# EEZ_PSU_post-regulator_r4B45.net
KiCad netlist of a schematic drawn in EAGLE
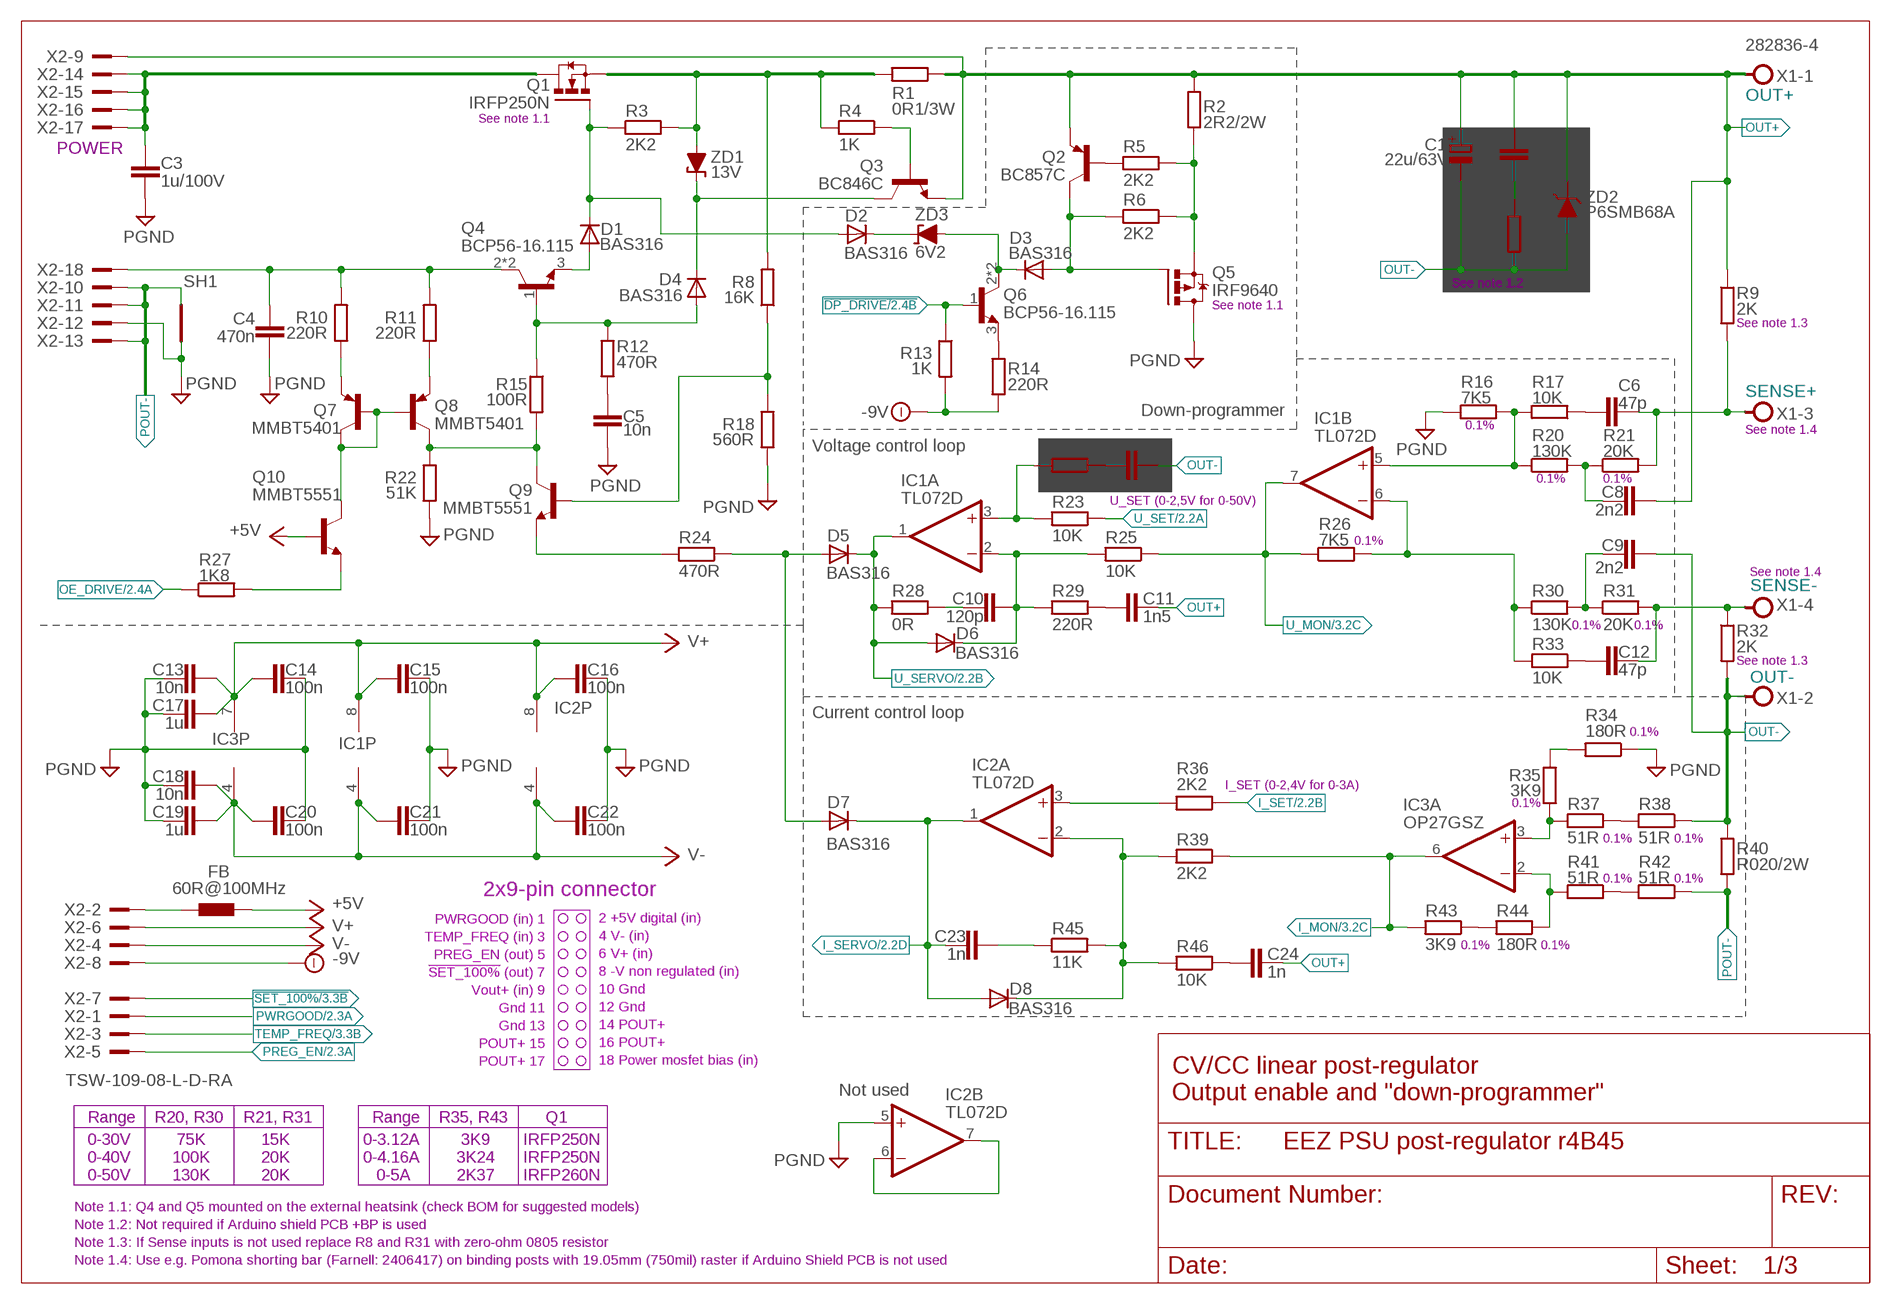
[diagram p0: schematic, sheet 1]
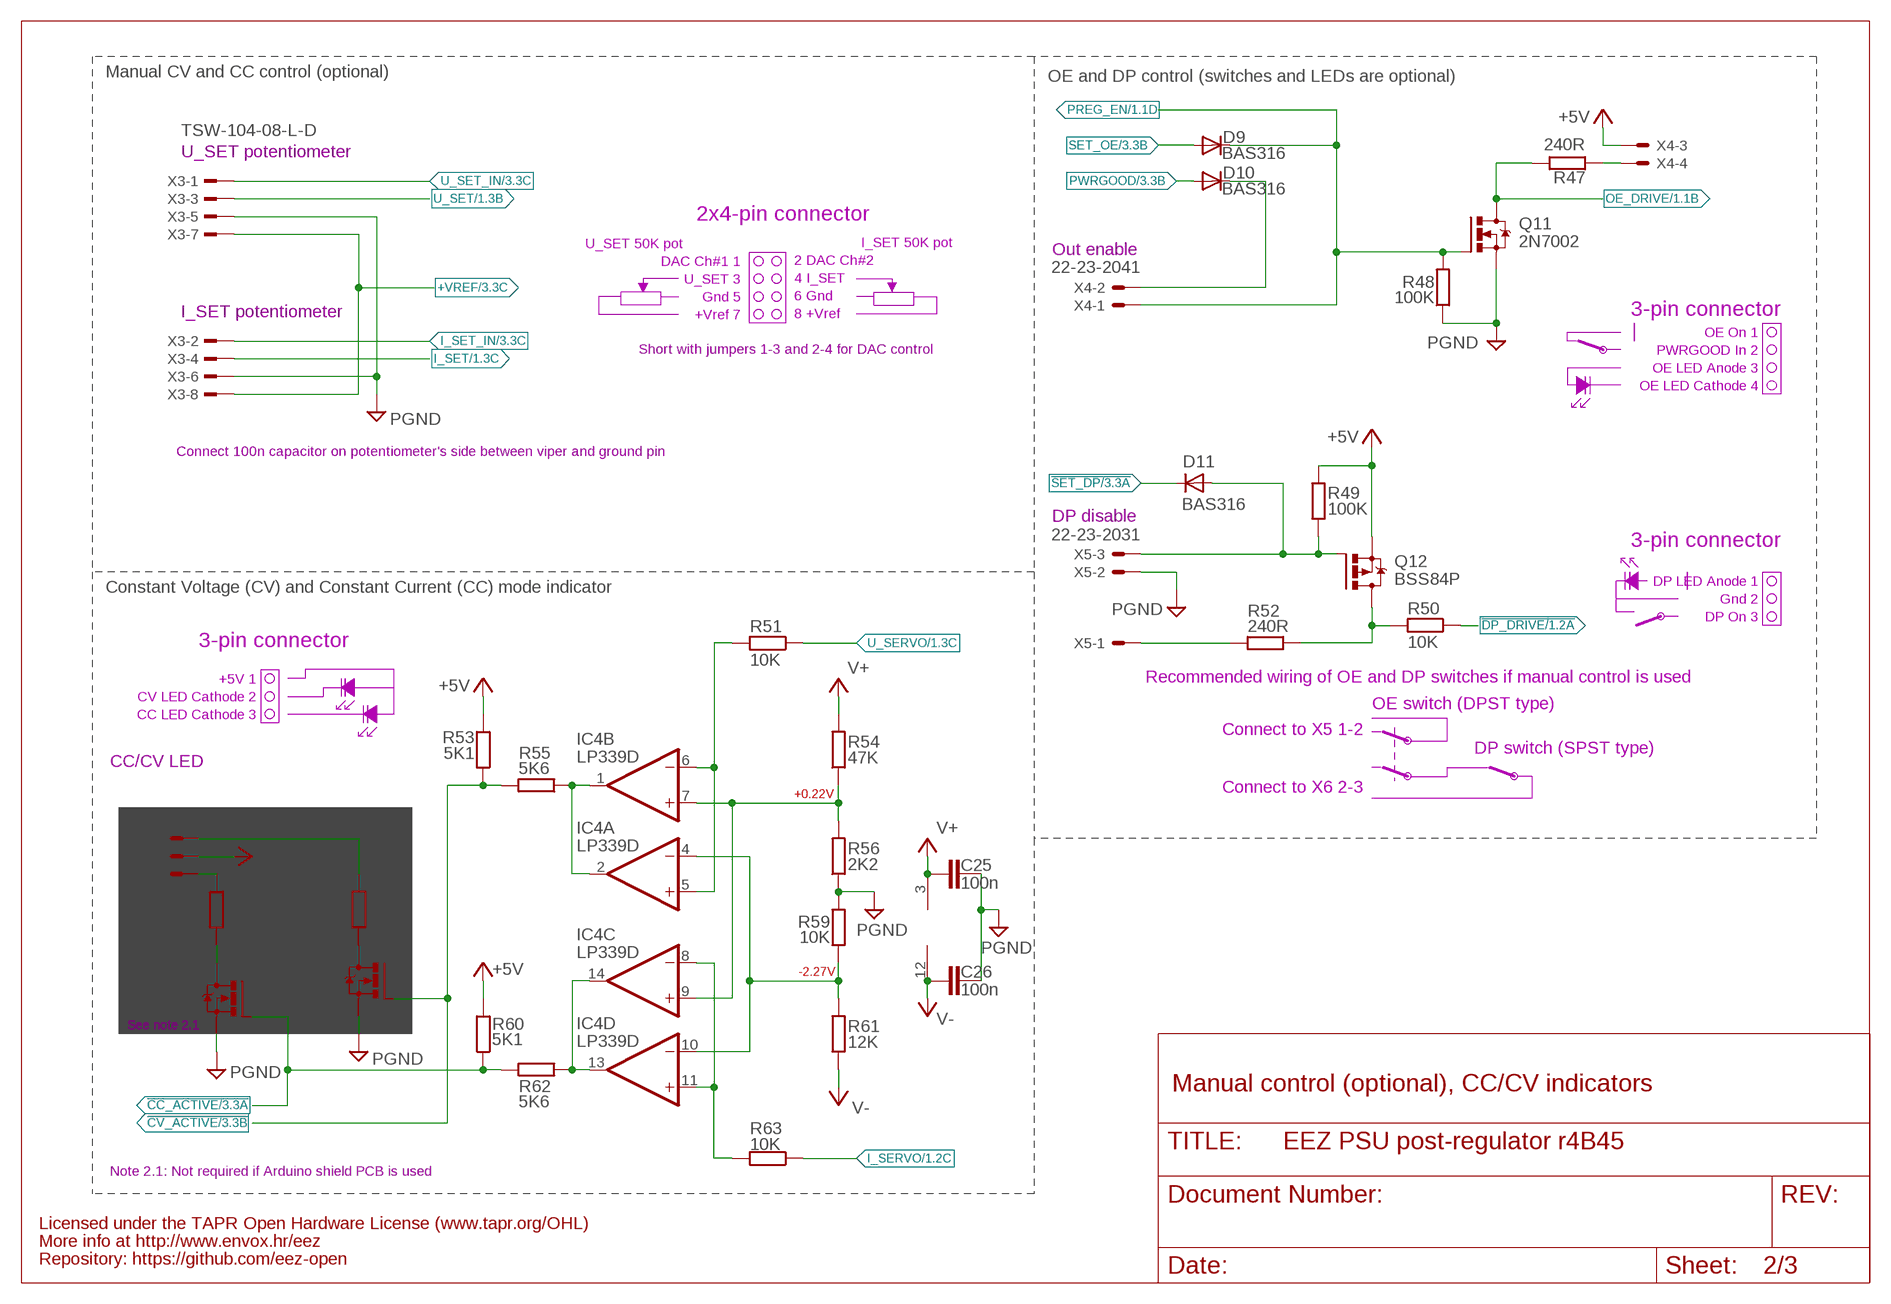
[diagram p1: schematic, sheet 2]
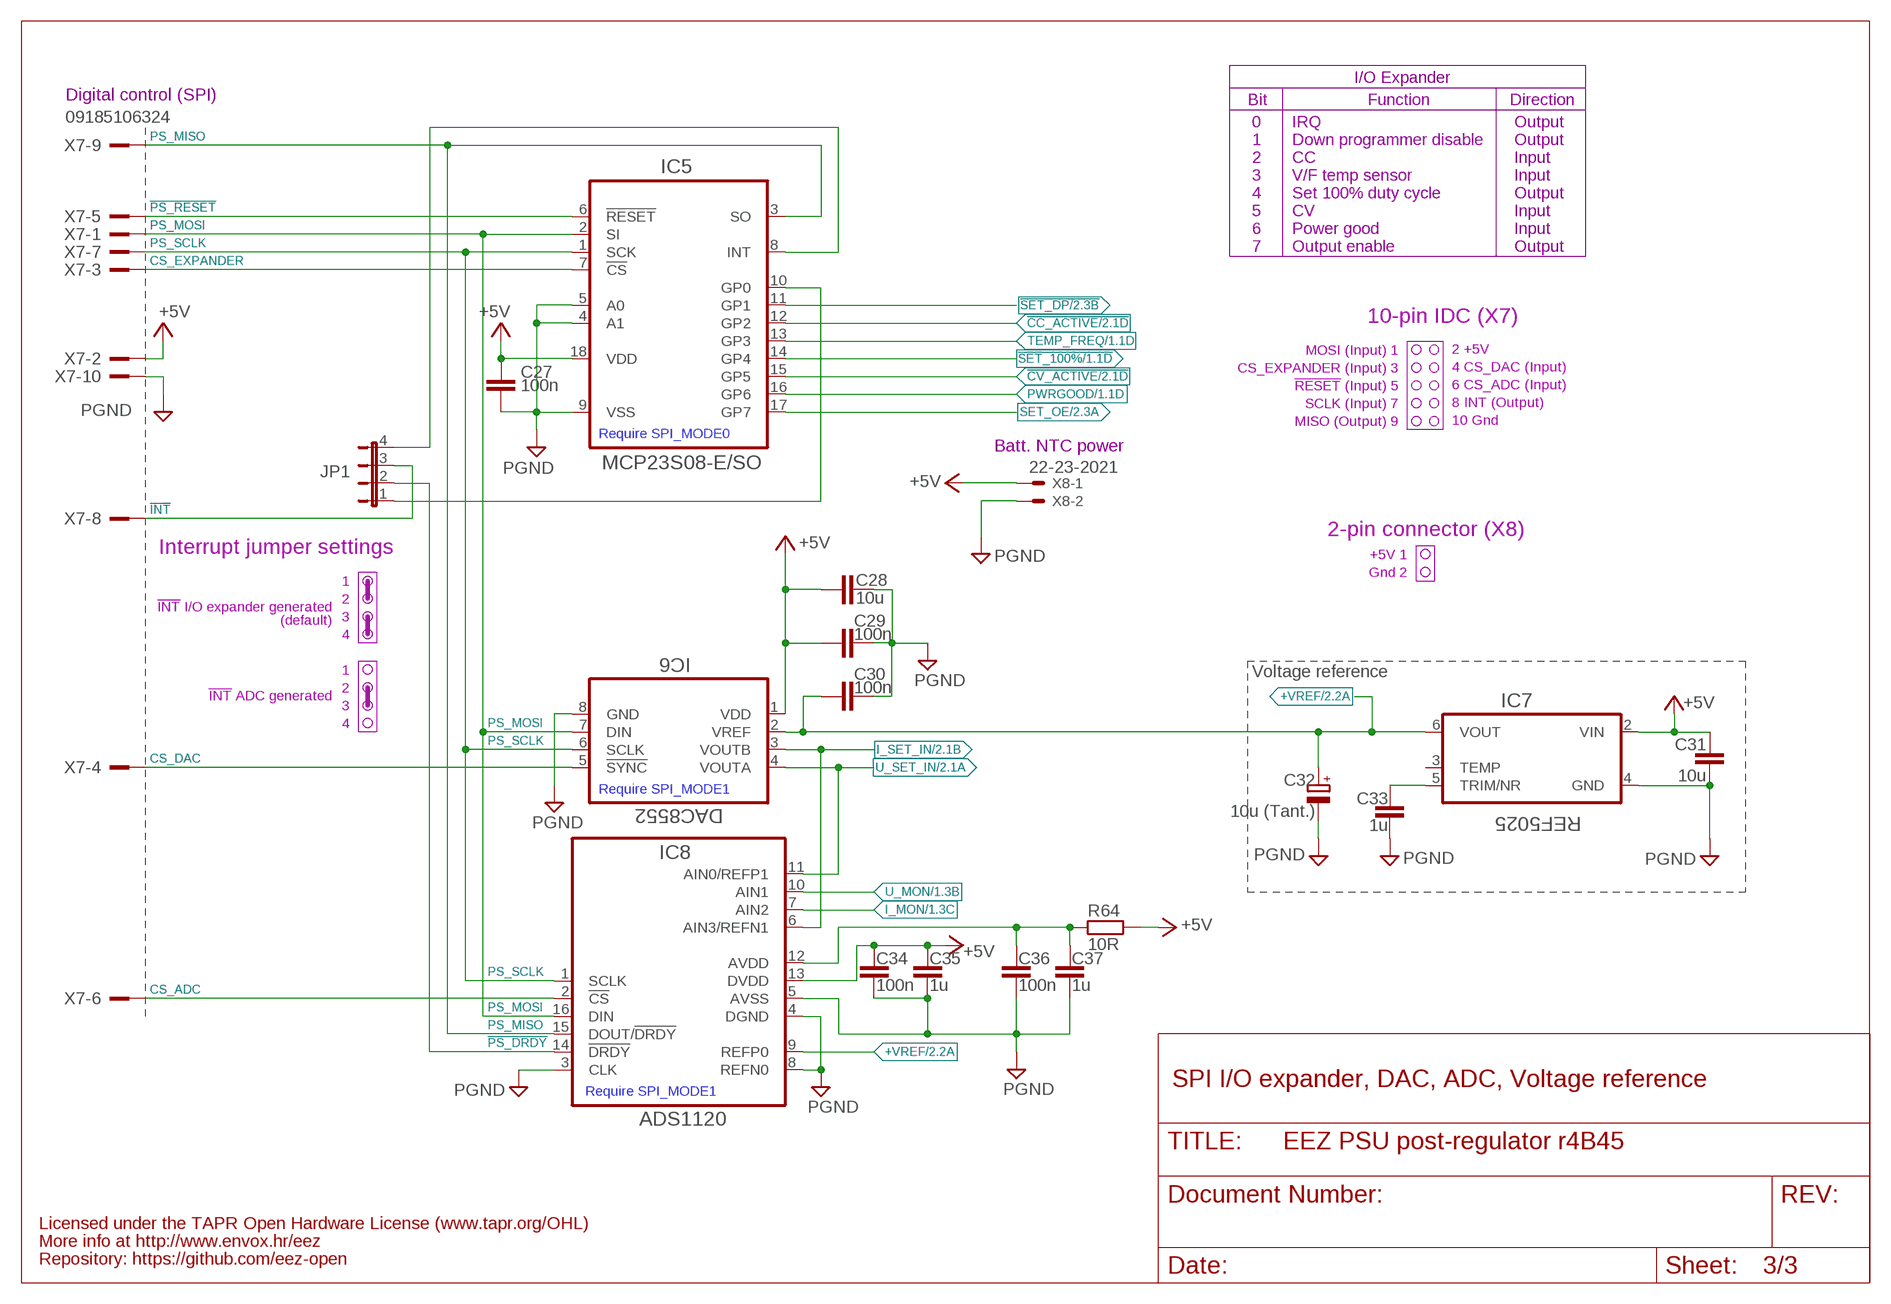
[diagram p2: schematic, sheet 3]

(export (version "E")
  (design (tool "Eeschema 10.0.6"))
  (components
    (comp (ref "C1")
      (value "22u/63V")
      (footprint "eagle-import:CAPAE660X610N_COMBO2")
      (libsource (lib "eagle-import") (part "ECAPEEEFK+2.5MM"))
    )
    (comp (ref "C2")
      (value "470n")
      (footprint "eagle-import:C1812")
      (libsource (lib "eagle-import") (part "C-EUC1812"))
    )
    (comp (ref "C3")
      (value "1u/100V")
      (footprint "eagle-import:C1206")
      (libsource (lib "eagle-import") (part "C-EUC1206"))
    )
    (comp (ref "C4")
      (value "470n")
      (footprint "eagle-import:C1812")
      (libsource (lib "eagle-import") (part "C-EUC1812"))
    )
    (comp (ref "C5")
      (value "10n")
      (footprint "eagle-import:C0805")
      (libsource (lib "eagle-import") (part "C-EUC0805"))
    )
    (comp (ref "C6")
      (value "47p")
      (footprint "eagle-import:C0805")
      (libsource (lib "eagle-import") (part "C-EUC0805"))
    )
    (comp (ref "C7")
      (value "1n5")
      (footprint "eagle-import:C0805")
      (libsource (lib "eagle-import") (part "C-EUC0805"))
    )
    (comp (ref "C8")
      (value "2n2")
      (footprint "eagle-import:C0805")
      (libsource (lib "eagle-import") (part "C-EUC0805"))
    )
    (comp (ref "C9")
      (value "2n2")
      (footprint "eagle-import:C0805")
      (libsource (lib "eagle-import") (part "C-EUC0805"))
    )
    (comp (ref "C10")
      (value "120p")
      (footprint "eagle-import:C0805")
      (libsource (lib "eagle-import") (part "C-EUC0805"))
    )
    (comp (ref "C11")
      (value "1n5")
      (footprint "eagle-import:C0805")
      (libsource (lib "eagle-import") (part "C-EUC0805"))
    )
    (comp (ref "C12")
      (value "47p")
      (footprint "eagle-import:C0805")
      (libsource (lib "eagle-import") (part "C-EUC0805"))
    )
    (comp (ref "C13")
      (value "10n")
      (footprint "eagle-import:C0805")
      (libsource (lib "eagle-import") (part "C-EUC0805"))
    )
    (comp (ref "C14")
      (value "100n")
      (footprint "eagle-import:C0603")
      (libsource (lib "eagle-import") (part "C-EUC0603"))
    )
    (comp (ref "C15")
      (value "100n")
      (footprint "eagle-import:C0603")
      (libsource (lib "eagle-import") (part "C-EUC0603"))
    )
    (comp (ref "C16")
      (value "100n")
      (footprint "eagle-import:C0603")
      (libsource (lib "eagle-import") (part "C-EUC0603"))
    )
    (comp (ref "C17")
      (value "1u")
      (footprint "eagle-import:C0805")
      (libsource (lib "eagle-import") (part "C-EUC0805"))
    )
    (comp (ref "C18")
      (value "10n")
      (footprint "eagle-import:C0805")
      (libsource (lib "eagle-import") (part "C-EUC0805"))
    )
    (comp (ref "C19")
      (value "1u")
      (footprint "eagle-import:C0805")
      (libsource (lib "eagle-import") (part "C-EUC0805"))
    )
    (comp (ref "C20")
      (value "100n")
      (footprint "eagle-import:C0603")
      (libsource (lib "eagle-import") (part "C-EUC0603"))
    )
    (comp (ref "C21")
      (value "100n")
      (footprint "eagle-import:C0603")
      (libsource (lib "eagle-import") (part "C-EUC0603"))
    )
    (comp (ref "C22")
      (value "100n")
      (footprint "eagle-import:C0603")
      (libsource (lib "eagle-import") (part "C-EUC0603"))
    )
    (comp (ref "C23")
      (value "1n")
      (footprint "eagle-import:C0805")
      (libsource (lib "eagle-import") (part "C-EUC0805"))
    )
    (comp (ref "C24")
      (value "1n")
      (footprint "eagle-import:C0805")
      (libsource (lib "eagle-import") (part "C-EUC0805"))
    )
    (comp (ref "D1")
      (value "BAS316")
      (footprint "eagle-import:SOD323-W")
      (libsource (lib "eagle-import") (part "DIODE-SOD323-W"))
    )
    (comp (ref "D2")
      (value "BAS316")
      (footprint "eagle-import:SOD323-W")
      (libsource (lib "eagle-import") (part "DIODE-SOD323-W"))
    )
    (comp (ref "D3")
      (value "BAS316")
      (footprint "eagle-import:SOD323-W")
      (libsource (lib "eagle-import") (part "DIODE-SOD323-W"))
    )
    (comp (ref "D4")
      (value "BAS316")
      (footprint "eagle-import:SOD323-W")
      (libsource (lib "eagle-import") (part "DIODE-SOD323-W"))
    )
    (comp (ref "D5")
      (value "BAS316")
      (footprint "eagle-import:SOD323-W")
      (libsource (lib "eagle-import") (part "DIODE-SOD323-W"))
    )
    (comp (ref "D6")
      (value "BAS316")
      (footprint "eagle-import:SOD323-W")
      (libsource (lib "eagle-import") (part "DIODE-SOD323-W"))
    )
    (comp (ref "D7")
      (value "BAS316")
      (footprint "eagle-import:SOD323-W")
      (libsource (lib "eagle-import") (part "DIODE-SOD323-W"))
    )
    (comp (ref "D8")
      (value "BAS316")
      (footprint "eagle-import:SOD323-W")
      (libsource (lib "eagle-import") (part "DIODE-SOD323-W"))
    )
    (comp (ref "FB")
      (value "60R@100MHz")
      (footprint "eagle-import:BEAD0603")
      (libsource (lib "eagle-import") (part "FERRITE_BEAD0603"))
    )
    (comp (ref "IC1")
      (value "TL072D")
      (footprint "eagle-import:SOIC127P600X173-8N")
      (libsource (lib "eagle-import") (part "TL072SOIC8"))
    )
    (comp (ref "IC2")
      (value "TL072D")
      (footprint "eagle-import:SOIC127P600X173-8N")
      (libsource (lib "eagle-import") (part "TL072SOIC8"))
    )
    (comp (ref "IC3")
      (value "OP27GSZ")
      (footprint "eagle-import:SOIC127P600X173-8N")
      (libsource (lib "eagle-import") (part "OP27GSZSO8"))
    )
    (comp (ref "Q1")
      (value "IRFP250N")
      (footprint "eagle-import:TO247BV")
      (libsource (lib "eagle-import") (part "IRFP240"))
    )
    (comp (ref "Q2")
      (value "BC857C")
      (footprint "eagle-import:SOT23-BEC")
      (libsource (lib "eagle-import") (part "-PNP-SOT23-BECBC857C"))
    )
    (comp (ref "Q3")
      (value "BC846C")
      (footprint "eagle-import:SOT23-BEC")
      (libsource (lib "eagle-import") (part "-NPN-SOT23-BECBC846B"))
    )
    (comp (ref "Q4")
      (value "BCP56-16.115")
      (footprint "eagle-import:SOT230P700X180-4N")
      (libsource (lib "eagle-import") (part "BCP56"))
    )
    (comp (ref "Q5")
      (value "IRF9640")
      (footprint "eagle-import:TO220B-VMOS")
      (libsource (lib "eagle-import") (part "IRF9640"))
    )
    (comp (ref "Q6")
      (value "BCP56-16.115")
      (footprint "eagle-import:SOT230P700X180-4N")
      (libsource (lib "eagle-import") (part "BCP56"))
    )
    (comp (ref "Q7")
      (value "MMBT5401")
      (footprint "eagle-import:SOT23-BEC")
      (libsource (lib "eagle-import") (part "-PNP-SOT23-BECBC857B"))
    )
    (comp (ref "Q8")
      (value "MMBT5401")
      (footprint "eagle-import:SOT23-BEC")
      (libsource (lib "eagle-import") (part "-PNP-SOT23-BECBC857B"))
    )
    (comp (ref "Q9")
      (value "MMBT5551")
      (footprint "eagle-import:SOT23-BEC")
      (libsource (lib "eagle-import") (part "-NPN-SOT23-BECMMBT5551LT1"))
    )
    (comp (ref "Q10")
      (value "MMBT5551")
      (footprint "eagle-import:SOT23-BEC")
      (libsource (lib "eagle-import") (part "-NPN-SOT23-BECMMBT5551LT1"))
    )
    (comp (ref "R1")
      (value "0R1/3W")
      (footprint "eagle-import:0411V")
      (libsource (lib "eagle-import") (part "R-EU_0411/3V"))
    )
    (comp (ref "R2")
      (value "2R2/2W")
      (footprint "eagle-import:0411V")
      (libsource (lib "eagle-import") (part "R-EU_0411/3V"))
    )
    (comp (ref "R3")
      (value "2K2")
      (footprint "eagle-import:R0805")
      (libsource (lib "eagle-import") (part "R-EU_R0805"))
    )
    (comp (ref "R4")
      (value "1K")
      (footprint "eagle-import:R0805")
      (libsource (lib "eagle-import") (part "R-EU_R0805"))
    )
    (comp (ref "R5")
      (value "2K2")
      (footprint "eagle-import:R0805")
      (libsource (lib "eagle-import") (part "R-EU_R0805"))
    )
    (comp (ref "R6")
      (value "2K2")
      (footprint "eagle-import:R0805")
      (libsource (lib "eagle-import") (part "R-EU_R0805"))
    )
    (comp (ref "R7")
      (value "1R")
      (footprint "eagle-import:R0805")
      (libsource (lib "eagle-import") (part "R-EU_R0805"))
    )
    (comp (ref "R8")
      (value "16K")
      (footprint "eagle-import:R0805")
      (libsource (lib "eagle-import") (part "R-EU_R0805"))
    )
    (comp (ref "R9")
      (value "2K")
      (footprint "eagle-import:R0805")
      (libsource (lib "eagle-import") (part "R-EU_R0805"))
    )
    (comp (ref "R10")
      (value "220R")
      (footprint "eagle-import:R0805")
      (libsource (lib "eagle-import") (part "R-EU_R0805"))
    )
    (comp (ref "R11")
      (value "220R")
      (footprint "eagle-import:R0805")
      (libsource (lib "eagle-import") (part "R-EU_R0805"))
    )
    (comp (ref "R12")
      (value "470R")
      (footprint "eagle-import:R0805")
      (libsource (lib "eagle-import") (part "R-EU_R0805"))
    )
    (comp (ref "R13")
      (value "1K")
      (footprint "eagle-import:R0805")
      (libsource (lib "eagle-import") (part "R-EU_R0805"))
    )
    (comp (ref "R14")
      (value "220R")
      (footprint "eagle-import:R0805")
      (libsource (lib "eagle-import") (part "R-EU_R0805"))
    )
    (comp (ref "R15")
      (value "100R")
      (footprint "eagle-import:R0805")
      (libsource (lib "eagle-import") (part "R-EU_R0805"))
    )
    (comp (ref "R16")
      (value "7K5")
      (footprint "eagle-import:R0805")
      (libsource (lib "eagle-import") (part "R-EU_R0805"))
    )
    (comp (ref "R17")
      (value "10K")
      (footprint "eagle-import:R0805")
      (libsource (lib "eagle-import") (part "R-EU_R0805"))
    )
    (comp (ref "R18")
      (value "560R")
      (footprint "eagle-import:R0805")
      (libsource (lib "eagle-import") (part "R-EU_R0805"))
    )
    (comp (ref "R19")
      (value "220R")
      (footprint "eagle-import:R0805")
      (libsource (lib "eagle-import") (part "R-EU_R0805"))
    )
    (comp (ref "R20")
      (value "130K")
      (footprint "eagle-import:R0805")
      (libsource (lib "eagle-import") (part "R-EU_R0805"))
    )
    (comp (ref "R21")
      (value "20K")
      (footprint "eagle-import:R0805")
      (libsource (lib "eagle-import") (part "R-EU_R0805"))
    )
    (comp (ref "R22")
      (value "51K")
      (footprint "eagle-import:R0805")
      (libsource (lib "eagle-import") (part "R-EU_R0805"))
    )
    (comp (ref "R23")
      (value "10K")
      (footprint "eagle-import:R0805")
      (libsource (lib "eagle-import") (part "R-EU_R0805"))
    )
    (comp (ref "R24")
      (value "470R")
      (footprint "eagle-import:R0805")
      (libsource (lib "eagle-import") (part "R-EU_R0805"))
    )
    (comp (ref "R25")
      (value "10K")
      (footprint "eagle-import:R0805")
      (libsource (lib "eagle-import") (part "R-EU_R0805"))
    )
    (comp (ref "R26")
      (value "7K5")
      (footprint "eagle-import:R0805")
      (libsource (lib "eagle-import") (part "R-EU_R0805"))
    )
    (comp (ref "R27")
      (value "1K8")
      (footprint "eagle-import:R0805")
      (libsource (lib "eagle-import") (part "R-EU_R0805"))
    )
    (comp (ref "R28")
      (value "0R")
      (footprint "eagle-import:R0805")
      (libsource (lib "eagle-import") (part "R-EU_R0805"))
    )
    (comp (ref "R29")
      (value "220R")
      (footprint "eagle-import:R0805")
      (libsource (lib "eagle-import") (part "R-EU_R0805"))
    )
    (comp (ref "R30")
      (value "130K")
      (footprint "eagle-import:R0805")
      (libsource (lib "eagle-import") (part "R-EU_R0805"))
    )
    (comp (ref "R31")
      (value "20K")
      (footprint "eagle-import:R0805")
      (libsource (lib "eagle-import") (part "R-EU_R0805"))
    )
    (comp (ref "R32")
      (value "2K")
      (footprint "eagle-import:R0805")
      (libsource (lib "eagle-import") (part "R-EU_R0805"))
    )
    (comp (ref "R33")
      (value "10K")
      (footprint "eagle-import:R0805")
      (libsource (lib "eagle-import") (part "R-EU_R0805"))
    )
    (comp (ref "R34")
      (value "180R")
      (footprint "eagle-import:R0805")
      (libsource (lib "eagle-import") (part "R-EU_R0805"))
    )
    (comp (ref "R35")
      (value "3K9")
      (footprint "eagle-import:R0805")
      (libsource (lib "eagle-import") (part "R-EU_R0805"))
    )
    (comp (ref "R36")
      (value "2K2")
      (footprint "eagle-import:R0805")
      (libsource (lib "eagle-import") (part "R-EU_R0805"))
    )
    (comp (ref "R37")
      (value "51R")
      (footprint "eagle-import:R0805")
      (libsource (lib "eagle-import") (part "R-EU_R0805"))
    )
    (comp (ref "R38")
      (value "51R")
      (footprint "eagle-import:R0805")
      (libsource (lib "eagle-import") (part "R-EU_R0805"))
    )
    (comp (ref "R39")
      (value "2K2")
      (footprint "eagle-import:R0805")
      (libsource (lib "eagle-import") (part "R-EU_R0805"))
    )
    (comp (ref "R40")
      (value "R020/2W")
      (footprint "eagle-import:R2512")
      (libsource (lib "eagle-import") (part "R-EU_R2512"))
    )
    (comp (ref "R41")
      (value "51R")
      (footprint "eagle-import:R0805")
      (libsource (lib "eagle-import") (part "R-EU_R0805"))
    )
    (comp (ref "R42")
      (value "51R")
      (footprint "eagle-import:R0805")
      (libsource (lib "eagle-import") (part "R-EU_R0805"))
    )
    (comp (ref "R43")
      (value "3K9")
      (footprint "eagle-import:R0805")
      (libsource (lib "eagle-import") (part "R-EU_R0805"))
    )
    (comp (ref "R44")
      (value "180R")
      (footprint "eagle-import:R0805")
      (libsource (lib "eagle-import") (part "R-EU_R0805"))
    )
    (comp (ref "R45")
      (value "11K")
      (footprint "eagle-import:R0805")
      (libsource (lib "eagle-import") (part "R-EU_R0805"))
    )
    (comp (ref "R46")
      (value "10K")
      (footprint "eagle-import:R0805")
      (libsource (lib "eagle-import") (part "R-EU_R0805"))
    )
    (comp (ref "SH1")
      (value "GND")
      (footprint "eagle-import:SHORT")
      (libsource (lib "eagle-import") (part "SHORT"))
    )
    (comp (ref "X1")
      (value "282836-4")
      (footprint "eagle-import:TBLOCK5.0_4")
      (libsource (lib "eagle-import") (part "TBLOCK5.0_4A"))
    )
    (comp (ref "X2")
      (value "TSW-109-08-L-D-RA")
      (footprint "eagle-import:TSW-109-08-L-D-RA")
      (fields (field (name "FARNELL") "2032801"))
      (libsource (lib "eagle-import") (part "TSW-109-08-L-D-RA"))
    )
    (comp (ref "ZD1")
      (value "13V")
      (footprint "eagle-import:MINIMELF")
      (libsource (lib "eagle-import") (part "ZENER-DIODEMINIMELF"))
    )
    (comp (ref "ZD2")
      (value "P6SMB68A")
      (footprint "eagle-import:DO214AA")
      (libsource (lib "eagle-import") (part "P6SMB68A"))
    )
    (comp (ref "ZD3")
      (value "6V2")
      (footprint "eagle-import:MINIMELF")
      (libsource (lib "eagle-import") (part "ZENER-DIODEMINIMELF"))
    )
    (comp (ref "C27")
      (value "100n")
      (footprint "eagle-import:C0603")
      (libsource (lib "eagle-import") (part "C-EUC0603"))
    )
    (comp (ref "C28")
      (value "10u")
      (footprint "eagle-import:C1206")
      (libsource (lib "eagle-import") (part "C-EUC1206"))
    )
    (comp (ref "C29")
      (value "100n")
      (footprint "eagle-import:C0603")
      (libsource (lib "eagle-import") (part "C-EUC0603"))
    )
    (comp (ref "C30")
      (value "100n")
      (footprint "eagle-import:C0603")
      (libsource (lib "eagle-import") (part "C-EUC0603"))
    )
    (comp (ref "C31")
      (value "10u")
      (footprint "eagle-import:C1206")
      (libsource (lib "eagle-import") (part "C-EUC1206"))
    )
    (comp (ref "C32")
      (value "10u (Tant.)")
      (footprint "eagle-import:EC1206")
      (libsource (lib "eagle-import") (part "ECAP1206"))
    )
    (comp (ref "C33")
      (value "1u")
      (footprint "eagle-import:C0805")
      (libsource (lib "eagle-import") (part "C-EUC0805"))
    )
    (comp (ref "C34")
      (value "100n")
      (footprint "eagle-import:C0603")
      (libsource (lib "eagle-import") (part "C-EUC0603"))
    )
    (comp (ref "C35")
      (value "1u")
      (footprint "eagle-import:C0805")
      (libsource (lib "eagle-import") (part "C-EUC0805"))
    )
    (comp (ref "C36")
      (value "100n")
      (footprint "eagle-import:C0603")
      (libsource (lib "eagle-import") (part "C-EUC0603"))
    )
    (comp (ref "C37")
      (value "1u")
      (footprint "eagle-import:C0805")
      (libsource (lib "eagle-import") (part "C-EUC0805"))
    )
    (comp (ref "IC5")
      (value "MCP23S08-E/SO")
      (footprint "eagle-import:SOIC127P1030X265-18N")
      (libsource (lib "eagle-import") (part "MCP23S08"))
    )
    (comp (ref "IC6")
      (value "DAC8552")
      (footprint "eagle-import:DGK8-M")
      (libsource (lib "eagle-import") (part "DAC8552_DGK_8M"))
    )
    (comp (ref "IC7")
      (value "REF5025")
      (footprint "eagle-import:SOIC127P600X175-8N")
      (libsource (lib "eagle-import") (part "REF50XX"))
    )
    (comp (ref "IC8")
      (value "ADS1120")
      (footprint "eagle-import:PW(R-PDSO-G16)")
      (libsource (lib "eagle-import") (part "ADS1120TSSOP-16"))
    )
    (comp (ref "JP1")
      (value "JP4E")
      (footprint "eagle-import:JP4")
      (libsource (lib "eagle-import") (part "JP4E"))
    )
    (comp (ref "R64")
      (value "10R")
      (footprint "eagle-import:R0805")
      (libsource (lib "eagle-import") (part "R-EU_R0805"))
    )
    (comp (ref "X7")
      (value "09185106324")
      (footprint "eagle-import:PAK100_2500-10")
      (fields (field (name "MF") "3M") (field (name "MPN") "2510-6002UB"))
      (libsource (lib "eagle-import") (part "2510-"))
    )
    (comp (ref "X8")
      (value "22-23-2021")
      (footprint "eagle-import:22-23-2021")
      (fields
        (field (name "MF") "MOLEX")
        (field (name "MPN") "22-23-2021")
        (field (name "OC_FARNELL") "1462926")
        (field (name "OC_NEWARK") "25C3832")
      )
      (libsource (lib "eagle-import") (part "22-23-2021"))
    )
    (comp (ref "C25")
      (value "100n")
      (footprint "eagle-import:C0603")
      (libsource (lib "eagle-import") (part "C-EUC0603"))
    )
    (comp (ref "C26")
      (value "100n")
      (footprint "eagle-import:C0603")
      (libsource (lib "eagle-import") (part "C-EUC0603"))
    )
    (comp (ref "D9")
      (value "BAS316")
      (footprint "eagle-import:SOD323-W")
      (libsource (lib "eagle-import") (part "DIODE-SOD323-W"))
    )
    (comp (ref "D10")
      (value "BAS316")
      (footprint "eagle-import:SOD323-W")
      (libsource (lib "eagle-import") (part "DIODE-SOD323-W"))
    )
    (comp (ref "D11")
      (value "BAS316")
      (footprint "eagle-import:SOD323-W")
      (libsource (lib "eagle-import") (part "DIODE-SOD323-W"))
    )
    (comp (ref "IC4")
      (value "LP339D")
      (footprint "eagle-import:SO14")
      (libsource (lib "eagle-import") (part "LM339D"))
    )
    (comp (ref "Q11")
      (value "2N7002")
      (footprint "eagle-import:SOT103P240X110-3N")
      (fields
        (field (name "MPN") "2N7002-7-F")
        (field (name "MPN_1") "2N7002-7-F")
        (field (name "OC_FARNELL") "1713823")
        (field (name "OC_NEWARK") "25R5679")
        (field (name "PACKAGE") "SOT-23-3")
        (field (name "SUPPLIER") "DIODES INC.")
      )
      (libsource (lib "eagle-import") (part "2N7002"))
    )
    (comp (ref "Q12")
      (value "BSS84P")
      (footprint "eagle-import:SOT95P237X112-3N")
      (fields (field (name "MPN") "IRLML2246TRPBF"))
      (libsource (lib "eagle-import") (part "IRLML2246TRPBF"))
    )
    (comp (ref "Q13")
      (value "2N7002")
      (footprint "eagle-import:SOT103P240X110-3N")
      (fields (field (name "MPN") "2N7002-7-F"))
      (libsource (lib "eagle-import") (part "2N7002"))
    )
    (comp (ref "Q14")
      (value "2N7002")
      (footprint "eagle-import:SOT103P240X110-3N")
      (fields (field (name "MPN") "2N7002-7-F"))
      (libsource (lib "eagle-import") (part "2N7002"))
    )
    (comp (ref "R47")
      (value "240R")
      (footprint "eagle-import:R0805")
      (libsource (lib "eagle-import") (part "R-EU_R0805"))
    )
    (comp (ref "R48")
      (value "100K")
      (footprint "eagle-import:R0805")
      (libsource (lib "eagle-import") (part "R-EU_R0805"))
    )
    (comp (ref "R49")
      (value "100K")
      (footprint "eagle-import:R0805")
      (libsource (lib "eagle-import") (part "R-EU_R0805"))
    )
    (comp (ref "R50")
      (value "10K")
      (footprint "eagle-import:R0805")
      (libsource (lib "eagle-import") (part "R-EU_R0805"))
    )
    (comp (ref "R51")
      (value "10K")
      (footprint "eagle-import:R0805")
      (libsource (lib "eagle-import") (part "R-EU_R0805"))
    )
    (comp (ref "R52")
      (value "240R")
      (footprint "eagle-import:R0805")
      (libsource (lib "eagle-import") (part "R-EU_R0805"))
    )
    (comp (ref "R53")
      (value "5K1")
      (footprint "eagle-import:R0805")
      (libsource (lib "eagle-import") (part "R-EU_R0805"))
    )
    (comp (ref "R54")
      (value "47K")
      (footprint "eagle-import:R0805")
      (libsource (lib "eagle-import") (part "R-EU_R0805"))
    )
    (comp (ref "R55")
      (value "5K6")
      (footprint "eagle-import:R0805")
      (libsource (lib "eagle-import") (part "R-EU_R0805"))
    )
    (comp (ref "R56")
      (value "2K2")
      (footprint "eagle-import:R0805")
      (libsource (lib "eagle-import") (part "R-EU_R0805"))
    )
    (comp (ref "R57")
      (value "240R")
      (footprint "eagle-import:R0805")
      (libsource (lib "eagle-import") (part "R-EU_R0805"))
    )
    (comp (ref "R58")
      (value "240R")
      (footprint "eagle-import:R0805")
      (libsource (lib "eagle-import") (part "R-EU_R0805"))
    )
    (comp (ref "R59")
      (value "10K")
      (footprint "eagle-import:R0805")
      (libsource (lib "eagle-import") (part "R-EU_R0805"))
    )
    (comp (ref "R60")
      (value "5K1")
      (footprint "eagle-import:R0805")
      (libsource (lib "eagle-import") (part "R-EU_R0805"))
    )
    (comp (ref "R61")
      (value "12K")
      (footprint "eagle-import:R0805")
      (libsource (lib "eagle-import") (part "R-EU_R0805"))
    )
    (comp (ref "R62")
      (value "5K6")
      (footprint "eagle-import:R0805")
      (libsource (lib "eagle-import") (part "R-EU_R0805"))
    )
    (comp (ref "R63")
      (value "10K")
      (footprint "eagle-import:R0805")
      (libsource (lib "eagle-import") (part "R-EU_R0805"))
    )
    (comp (ref "X3")
      (value "TSW-104-08-L-D")
      (footprint "eagle-import:TSW-104-02-S-D")
      (libsource (lib "eagle-import") (part "TSW-104-02-S-D"))
    )
    (comp (ref "X4")
      (value "22-23-2041")
      (footprint "eagle-import:22-23-2041")
      (fields
        (field (name "MF") "MOLEX")
        (field (name "MPN") "22-23-2041")
        (field (name "OC_FARNELL") "1462920")
        (field (name "OC_NEWARK") "38C0355")
      )
      (libsource (lib "eagle-import") (part "22-23-2041"))
    )
    (comp (ref "X5")
      (value "22-23-2031")
      (footprint "eagle-import:22-23-2031")
      (fields
        (field (name "MF") "MOLEX")
        (field (name "MF_1") "MOLEX")
        (field (name "MPN") "22-23-2031")
        (field (name "OC_FARNELL") "1462950")
        (field (name "OC_NEWARK") "30C0862")
      )
      (libsource (lib "eagle-import") (part "22-23-2031"))
    )
    (comp (ref "X6")
      (value "22-23-2031")
      (footprint "eagle-import:22-23-2031")
      (fields
        (field (name "MF") "MOLEX")
        (field (name "MPN") "22-23-2031")
        (field (name "OC_FARNELL") "1462950")
        (field (name "OC_NEWARK") "30C0862")
      )
      (libsource (lib "eagle-import") (part "22-23-2031"))
    )
  )
  (nets
    (net (code "1") (name "+5V") (class "Default")
      (node (ref "C27") (pin "1") (pinfunction "1_1") (pintype "passive"))
      (node (ref "C28") (pin "1") (pinfunction "1_1") (pintype "passive"))
      (node (ref "C29") (pin "2") (pinfunction "2_2") (pintype "passive"))
      (node (ref "C31") (pin "1") (pinfunction "1_1") (pintype "passive"))
      (node (ref "C34") (pin "2") (pinfunction "2_2") (pintype "passive"))
      (node (ref "C35") (pin "2") (pinfunction "2_2") (pintype "passive"))
      (node (ref "FB") (pin "P$2") (pinfunction "2_P$2") (pintype "passive"))
      (node (ref "IC5") (pin "18") (pinfunction "VDD_18") (pintype "power_in"))
      (node (ref "IC6") (pin "1") (pinfunction "VDD_1") (pintype "power_in"))
      (node (ref "IC7") (pin "2") (pinfunction "VIN_2") (pintype "passive"))
      (node (ref "IC8") (pin "13") (pinfunction "DVDD_13") (pintype "power_in"))
      (node (ref "Q10") (pin "B") (pinfunction "B_B") (pintype "passive"))
      (node (ref "Q12") (pin "2") (pinfunction "S_2") (pintype "passive"))
      (node (ref "R49") (pin "1") (pinfunction "1_1") (pintype "passive"))
      (node (ref "R53") (pin "2") (pinfunction "2_2") (pintype "passive"))
      (node (ref "R60") (pin "2") (pinfunction "2_2") (pintype "passive"))
      (node (ref "R64") (pin "1") (pinfunction "1_1") (pintype "passive"))
      (node (ref "X4") (pin "3") (pinfunction "S_3") (pintype "passive"))
      (node (ref "X6") (pin "2") (pinfunction "S_2") (pintype "passive"))
      (node (ref "X7") (pin "2") (pinfunction "KL_2") (pintype "passive"))
      (node (ref "X8") (pin "1") (pinfunction "S_1") (pintype "passive"))
    )
    (net (code "2") (name "+VREF") (class "Default")
      (node (ref "C30") (pin "2") (pinfunction "2_2") (pintype "passive"))
      (node (ref "C32") (pin "+") (pinfunction "+_+") (pintype "passive"))
      (node (ref "IC6") (pin "2") (pinfunction "VREF_2") (pintype "input"))
      (node (ref "IC7") (pin "6") (pinfunction "VOUT_6") (pintype "output"))
      (node (ref "IC8") (pin "9") (pinfunction "REFP0_9") (pintype "input"))
      (node (ref "X3") (pin "7") (pinfunction "1_7") (pintype "passive"))
      (node (ref "X3") (pin "8") (pinfunction "1_8") (pintype "passive"))
    )
    (net (code "3") (name "-9V") (class "Default")
      (node (ref "R13") (pin "2") (pinfunction "2_2") (pintype "passive"))
      (node (ref "R14") (pin "2") (pinfunction "2_2") (pintype "passive"))
      (node (ref "X2") (pin "8") (pinfunction "KL_8") (pintype "passive"))
    )
    (net (code "4") (name "CS_ADC") (class "Default")
      (node (ref "IC8") (pin "2") (pinfunction "~{CS}_2") (pintype "input"))
      (node (ref "X7") (pin "6") (pinfunction "KL_6") (pintype "passive"))
    )
    (net (code "5") (name "CS_DAC") (class "Default")
      (node (ref "IC6") (pin "5") (pinfunction "~{SYNC}_5") (pintype "input"))
      (node (ref "X7") (pin "4") (pinfunction "KL_4") (pintype "passive"))
    )
    (net (code "6") (name "CS_EXPANDER") (class "Default")
      (node (ref "IC5") (pin "7") (pinfunction "~{CS}_7") (pintype "input"))
      (node (ref "X7") (pin "3") (pinfunction "KL_3") (pintype "passive"))
    )
    (net (code "7") (name "GND") (class "Default")
      (node (ref "C13") (pin "1") (pinfunction "1_1") (pintype "passive"))
      (node (ref "C14") (pin "2") (pinfunction "2_2") (pintype "passive"))
      (node (ref "C15") (pin "1") (pinfunction "1_1") (pintype "passive"))
      (node (ref "C16") (pin "1") (pinfunction "1_1") (pintype "passive"))
      (node (ref "C17") (pin "1") (pinfunction "1_1") (pintype "passive"))
      (node (ref "C18") (pin "1") (pinfunction "1_1") (pintype "passive"))
      (node (ref "C19") (pin "1") (pinfunction "1_1") (pintype "passive"))
      (node (ref "C20") (pin "2") (pinfunction "2_2") (pintype "passive"))
      (node (ref "C21") (pin "1") (pinfunction "1_1") (pintype "passive"))
      (node (ref "C22") (pin "1") (pinfunction "1_1") (pintype "passive"))
      (node (ref "C25") (pin "1") (pinfunction "1_1") (pintype "passive"))
      (node (ref "C26") (pin "1") (pinfunction "1_1") (pintype "passive"))
      (node (ref "C27") (pin "2") (pinfunction "2_2") (pintype "passive"))
      (node (ref "C28") (pin "2") (pinfunction "2_2") (pintype "passive"))
      (node (ref "C29") (pin "1") (pinfunction "1_1") (pintype "passive"))
      (node (ref "C3") (pin "2") (pinfunction "2_2") (pintype "passive"))
      (node (ref "C30") (pin "1") (pinfunction "1_1") (pintype "passive"))
      (node (ref "C31") (pin "2") (pinfunction "2_2") (pintype "passive"))
      (node (ref "C32") (pin "-") (pinfunction "-_-") (pintype "passive"))
      (node (ref "C33") (pin "2") (pinfunction "2_2") (pintype "passive"))
      (node (ref "C34") (pin "1") (pinfunction "1_1") (pintype "passive"))
      (node (ref "C35") (pin "1") (pinfunction "1_1") (pintype "passive"))
      (node (ref "C36") (pin "1") (pinfunction "1_1") (pintype "passive"))
      (node (ref "C37") (pin "1") (pinfunction "1_1") (pintype "passive"))
      (node (ref "C4") (pin "2") (pinfunction "2_2") (pintype "passive"))
      (node (ref "C5") (pin "2") (pinfunction "2_2") (pintype "passive"))
      (node (ref "IC2") (pin "5") (pinfunction "+IN_5") (pintype "input"))
      (node (ref "IC5") (pin "4") (pinfunction "A1_4") (pintype "input"))
      (node (ref "IC5") (pin "5") (pinfunction "A0_5") (pintype "input"))
      (node (ref "IC5") (pin "9") (pinfunction "VSS_9") (pintype "power_in"))
      (node (ref "IC6") (pin "8") (pinfunction "GND_8") (pintype "power_in"))
      (node (ref "IC7") (pin "4") (pinfunction "GND_4") (pintype "passive"))
      (node (ref "IC8") (pin "3") (pinfunction "CLK_3") (pintype "bidirectional"))
      (node (ref "IC8") (pin "4") (pinfunction "DGND_4") (pintype "power_in"))
      (node (ref "IC8") (pin "5") (pinfunction "AVSS_5") (pintype "power_in"))
      (node (ref "IC8") (pin "8") (pinfunction "REFN0_8") (pintype "input"))
      (node (ref "Q11") (pin "2") (pinfunction "S_2") (pintype "passive"))
      (node (ref "Q13") (pin "2") (pinfunction "S_2") (pintype "passive"))
      (node (ref "Q14") (pin "2") (pinfunction "S_2") (pintype "passive"))
      (node (ref "Q5") (pin "D") (pinfunction "D_D") (pintype "passive"))
      (node (ref "R16") (pin "1") (pinfunction "1_1") (pintype "passive"))
      (node (ref "R18") (pin "1") (pinfunction "1_1") (pintype "passive"))
      (node (ref "R22") (pin "1") (pinfunction "1_1") (pintype "passive"))
      (node (ref "R34") (pin "1") (pinfunction "1_1") (pintype "passive"))
      (node (ref "R48") (pin "1") (pinfunction "1_1") (pintype "passive"))
      (node (ref "R56") (pin "1") (pinfunction "1_1") (pintype "passive"))
      (node (ref "R59") (pin "2") (pinfunction "2_2") (pintype "passive"))
      (node (ref "SH1") (pin "1") (pinfunction "GND_A_1") (pintype "bidirectional"))
      (node (ref "X2") (pin "12") (pinfunction "KL_12") (pintype "passive"))
      (node (ref "X3") (pin "5") (pinfunction "1_5") (pintype "passive"))
      (node (ref "X3") (pin "6") (pinfunction "1_6") (pintype "passive"))
      (node (ref "X5") (pin "2") (pinfunction "S_2") (pintype "passive"))
      (node (ref "X7") (pin "10") (pinfunction "KL_10") (pintype "passive"))
      (node (ref "X8") (pin "2") (pinfunction "S_2") (pintype "passive"))
    )
    (net (code "8") (name "I_MON") (class "Default")
      (node (ref "IC3") (pin "6") (pinfunction "OUT_6") (pintype "output"))
      (node (ref "IC8") (pin "7") (pinfunction "AIN2_7") (pintype "input"))
      (node (ref "R39") (pin "1") (pinfunction "1_1") (pintype "passive"))
      (node (ref "R43") (pin "2") (pinfunction "2_2") (pintype "passive"))
    )
    (net (code "9") (name "I_SERVO") (class "Default")
      (node (ref "C23") (pin "2") (pinfunction "2_2") (pintype "passive"))
      (node (ref "D7") (pin "C") (pinfunction "C_C") (pintype "passive"))
      (node (ref "D8") (pin "A") (pinfunction "A_A") (pintype "passive"))
      (node (ref "IC2") (pin "1") (pinfunction "OUT_1") (pintype "output"))
      (node (ref "R63") (pin "1") (pinfunction "1_1") (pintype "passive"))
    )
    (net (code "10") (name "I_SET") (class "Default")
      (node (ref "R36") (pin "1") (pinfunction "1_1") (pintype "passive"))
      (node (ref "X3") (pin "4") (pinfunction "1_4") (pintype "passive"))
    )
    (net (code "11") (name "I_SET_IN") (class "Default")
      (node (ref "IC6") (pin "3") (pinfunction "VOUTB_3") (pintype "output"))
      (node (ref "IC8") (pin "6") (pinfunction "AIN3/REFN1_6") (pintype "input"))
      (node (ref "X3") (pin "2") (pinfunction "1_2") (pintype "passive"))
    )
    (net (code "12") (name "Net-(C2-Pad2)") (class "Default")
      (node (ref "C2") (pin "2") (pinfunction "2_2") (pintype "passive"))
      (node (ref "R7") (pin "2") (pinfunction "2_2") (pintype "passive"))
    )
    (net (code "13") (name "Net-(C5-Pad1)") (class "Default")
      (node (ref "C5") (pin "1") (pinfunction "1_1") (pintype "passive"))
      (node (ref "R12") (pin "1") (pinfunction "1_1") (pintype "passive"))
    )
    (net (code "14") (name "Net-(C6-Pad2)") (class "Default")
      (node (ref "C6") (pin "2") (pinfunction "2_2") (pintype "passive"))
      (node (ref "R17") (pin "1") (pinfunction "1_1") (pintype "passive"))
    )
    (net (code "15") (name "Net-(C7-Pad2)") (class "Default")
      (node (ref "C7") (pin "2") (pinfunction "2_2") (pintype "passive"))
      (node (ref "R19") (pin "1") (pinfunction "1_1") (pintype "passive"))
    )
    (net (code "16") (name "Net-(C8-Pad1)") (class "Default")
      (node (ref "C8") (pin "1") (pinfunction "1_1") (pintype "passive"))
      (node (ref "R20") (pin "2") (pinfunction "2_2") (pintype "passive"))
      (node (ref "R21") (pin "1") (pinfunction "1_1") (pintype "passive"))
    )
    (net (code "17") (name "Net-(C9-Pad1)") (class "Default")
      (node (ref "C9") (pin "1") (pinfunction "1_1") (pintype "passive"))
      (node (ref "R30") (pin "2") (pinfunction "2_2") (pintype "passive"))
      (node (ref "R31") (pin "1") (pinfunction "1_1") (pintype "passive"))
    )
    (net (code "18") (name "Net-(C10-Pad2)") (class "Default")
      (node (ref "C10") (pin "2") (pinfunction "2_2") (pintype "passive"))
      (node (ref "R28") (pin "1") (pinfunction "1_1") (pintype "passive"))
    )
    (net (code "19") (name "Net-(C11-Pad2)") (class "Default")
      (node (ref "C11") (pin "2") (pinfunction "2_2") (pintype "passive"))
      (node (ref "R29") (pin "1") (pinfunction "1_1") (pintype "passive"))
    )
    (net (code "20") (name "Net-(C12-Pad2)") (class "Default")
      (node (ref "C12") (pin "2") (pinfunction "2_2") (pintype "passive"))
      (node (ref "R33") (pin "1") (pinfunction "1_1") (pintype "passive"))
    )
    (net (code "21") (name "Net-(C23-Pad1)") (class "Default")
      (node (ref "C23") (pin "1") (pinfunction "1_1") (pintype "passive"))
      (node (ref "R45") (pin "1") (pinfunction "1_1") (pintype "passive"))
    )
    (net (code "22") (name "Net-(C24-Pad2)") (class "Default")
      (node (ref "C24") (pin "2") (pinfunction "2_2") (pintype "passive"))
      (node (ref "R46") (pin "1") (pinfunction "1_1") (pintype "passive"))
    )
    (net (code "23") (name "Net-(D1-PadC)") (class "Default")
      (node (ref "D1") (pin "C") (pinfunction "C_C") (pintype "passive"))
      (node (ref "D2") (pin "A") (pinfunction "A_A") (pintype "passive"))
      (node (ref "Q1") (pin "G") (pinfunction "G_G") (pintype "passive"))
      (node (ref "R3") (pin "1") (pinfunction "1_1") (pintype "passive"))
    )
    (net (code "24") (name "Net-(D2-PadC)") (class "Default")
      (node (ref "D2") (pin "C") (pinfunction "C_C") (pintype "passive"))
      (node (ref "ZD3") (pin "C") (pinfunction "C_C") (pintype "passive"))
    )
    (net (code "25") (name "Net-(D3-PadA)") (class "Default")
      (node (ref "D3") (pin "A") (pinfunction "A_A") (pintype "passive"))
      (node (ref "Q2") (pin "C") (pinfunction "C_C") (pintype "passive"))
      (node (ref "Q5") (pin "G") (pinfunction "G_G") (pintype "passive"))
      (node (ref "R6") (pin "2") (pinfunction "2_2") (pintype "passive"))
    )
    (net (code "26") (name "Net-(D3-PadC)") (class "Default")
      (node (ref "D3") (pin "C") (pinfunction "C_C") (pintype "passive"))
      (node (ref "Q6") (pin "2") (pinfunction "C_2") (pintype "passive"))
      (node (ref "Q6") (pin "4") (pinfunction "C_4") (pintype "passive"))
      (node (ref "ZD3") (pin "A") (pinfunction "A_A") (pintype "passive"))
    )
    (net (code "27") (name "Net-(D4-PadC)") (class "Default")
      (node (ref "D4") (pin "C") (pinfunction "C_C") (pintype "passive"))
      (node (ref "Q3") (pin "C") (pinfunction "C_C") (pintype "passive"))
      (node (ref "ZD1") (pin "C") (pinfunction "C_C") (pintype "passive"))
    )
    (net (code "28") (name "Net-(D5-PadA)") (class "Default")
      (node (ref "D5") (pin "A") (pinfunction "A_A") (pintype "passive"))
      (node (ref "D7") (pin "A") (pinfunction "A_A") (pintype "passive"))
      (node (ref "R24") (pin "1") (pinfunction "1_1") (pintype "passive"))
    )
    (net (code "29") (name "Net-(FB-1)") (class "Default")
      (node (ref "FB") (pin "P$1") (pinfunction "1_P$1") (pintype "passive"))
      (node (ref "X2") (pin "2") (pinfunction "KL_2") (pintype "passive"))
    )
    (net (code "30") (name "Net-(IC1A-+IN)") (class "Default")
      (node (ref "IC1") (pin "3") (pinfunction "+IN_3") (pintype "input"))
      (node (ref "R19") (pin "2") (pinfunction "2_2") (pintype "passive"))
      (node (ref "R23") (pin "2") (pinfunction "2_2") (pintype "passive"))
    )
    (net (code "31") (name "Net-(IC1A--IN)") (class "Default")
      (node (ref "C10") (pin "1") (pinfunction "1_1") (pintype "passive"))
      (node (ref "D6") (pin "C") (pinfunction "C_C") (pintype "passive"))
      (node (ref "IC1") (pin "2") (pinfunction "-IN_2") (pintype "input"))
      (node (ref "R25") (pin "2") (pinfunction "2_2") (pintype "passive"))
      (node (ref "R29") (pin "2") (pinfunction "2_2") (pintype "passive"))
    )
    (net (code "32") (name "Net-(IC1B-+IN)") (class "Default")
      (node (ref "IC1") (pin "5") (pinfunction "+IN_5") (pintype "input"))
      (node (ref "R16") (pin "2") (pinfunction "2_2") (pintype "passive"))
      (node (ref "R17") (pin "2") (pinfunction "2_2") (pintype "passive"))
      (node (ref "R20") (pin "1") (pinfunction "1_1") (pintype "passive"))
    )
    (net (code "33") (name "Net-(IC1B--IN)") (class "Default")
      (node (ref "IC1") (pin "6") (pinfunction "-IN_6") (pintype "input"))
      (node (ref "R26") (pin "2") (pinfunction "2_2") (pintype "passive"))
      (node (ref "R30") (pin "1") (pinfunction "1_1") (pintype "passive"))
      (node (ref "R33") (pin "2") (pinfunction "2_2") (pintype "passive"))
    )
    (net (code "34") (name "Net-(IC2A-+IN)") (class "Default")
      (node (ref "IC2") (pin "3") (pinfunction "+IN_3") (pintype "input"))
      (node (ref "R36") (pin "2") (pinfunction "2_2") (pintype "passive"))
    )
    (net (code "35") (name "Net-(IC2A--IN)") (class "Default")
      (node (ref "D8") (pin "C") (pinfunction "C_C") (pintype "passive"))
      (node (ref "IC2") (pin "2") (pinfunction "-IN_2") (pintype "input"))
      (node (ref "R39") (pin "2") (pinfunction "2_2") (pintype "passive"))
      (node (ref "R45") (pin "2") (pinfunction "2_2") (pintype "passive"))
      (node (ref "R46") (pin "2") (pinfunction "2_2") (pintype "passive"))
    )
    (net (code "36") (name "Net-(IC2B--IN)") (class "Default")
      (node (ref "IC2") (pin "6") (pinfunction "-IN_6") (pintype "input"))
      (node (ref "IC2") (pin "7") (pinfunction "OUT_7") (pintype "output"))
    )
    (net (code "37") (name "Net-(IC3A-+IN)") (class "Default")
      (node (ref "IC3") (pin "3") (pinfunction "+IN_3") (pintype "input"))
      (node (ref "R35") (pin "2") (pinfunction "2_2") (pintype "passive"))
      (node (ref "R37") (pin "2") (pinfunction "2_2") (pintype "passive"))
    )
    (net (code "38") (name "Net-(IC3A--IN)") (class "Default")
      (node (ref "IC3") (pin "2") (pinfunction "-IN_2") (pintype "input"))
      (node (ref "R41") (pin "2") (pinfunction "2_2") (pintype "passive"))
      (node (ref "R44") (pin "1") (pinfunction "1_1") (pintype "passive"))
    )
    (net (code "39") (name "Net-(IC4A-+IN)") (class "Default")
      (node (ref "IC4") (pin "5") (pinfunction "+IN_5") (pintype "input"))
      (node (ref "IC4") (pin "6") (pinfunction "-IN_6") (pintype "input"))
      (node (ref "R51") (pin "2") (pinfunction "2_2") (pintype "passive"))
    )
    (net (code "40") (name "Net-(IC4A--IN)") (class "Default")
      (node (ref "IC4") (pin "10") (pinfunction "-IN_10") (pintype "input"))
      (node (ref "IC4") (pin "4") (pinfunction "-IN_4") (pintype "input"))
      (node (ref "R59") (pin "1") (pinfunction "1_1") (pintype "passive"))
      (node (ref "R61") (pin "2") (pinfunction "2_2") (pintype "passive"))
    )
    (net (code "41") (name "Net-(IC4A-OUT)") (class "Default")
      (node (ref "IC4") (pin "1") (pinfunction "OUT_1") (pintype "open_collector"))
      (node (ref "IC4") (pin "2") (pinfunction "OUT_2") (pintype "open_collector"))
      (node (ref "R55") (pin "1") (pinfunction "1_1") (pintype "passive"))
    )
    (net (code "42") (name "Net-(IC4B-+IN)") (class "Default")
      (node (ref "IC4") (pin "7") (pinfunction "+IN_7") (pintype "input"))
      (node (ref "IC4") (pin "9") (pinfunction "+IN_9") (pintype "input"))
      (node (ref "R54") (pin "1") (pinfunction "1_1") (pintype "passive"))
      (node (ref "R56") (pin "2") (pinfunction "2_2") (pintype "passive"))
    )
    (net (code "43") (name "Net-(IC4C--IN)") (class "Default")
      (node (ref "IC4") (pin "11") (pinfunction "+IN_11") (pintype "input"))
      (node (ref "IC4") (pin "8") (pinfunction "-IN_8") (pintype "input"))
      (node (ref "R63") (pin "2") (pinfunction "2_2") (pintype "passive"))
    )
    (net (code "44") (name "Net-(IC4C-OUT)") (class "Default")
      (node (ref "IC4") (pin "13") (pinfunction "OUT_13") (pintype "open_collector"))
      (node (ref "IC4") (pin "14") (pinfunction "OUT_14") (pintype "open_collector"))
      (node (ref "R62") (pin "1") (pinfunction "1_1") (pintype "passive"))
    )
    (net (code "45") (name "Net-(IC5-GP0)") (class "Default")
      (node (ref "IC5") (pin "10") (pinfunction "GP0_10") (pintype "bidirectional"))
      (node (ref "JP1") (pin "1") (pinfunction "1_1") (pintype "passive"))
    )
    (net (code "46") (name "Net-(IC5-INT)") (class "Default")
      (node (ref "IC5") (pin "8") (pinfunction "INT_8") (pintype "output"))
      (node (ref "JP1") (pin "4") (pinfunction "4_4") (pintype "passive"))
    )
    (net (code "47") (name "Net-(IC7-TRIM{slash}NR)") (class "Default")
      (node (ref "C33") (pin "1") (pinfunction "1_1") (pintype "passive"))
      (node (ref "IC7") (pin "5") (pinfunction "TRIM/NR_5") (pintype "input"))
    )
    (net (code "48") (name "Net-(IC8-AVDD)") (class "Default")
      (node (ref "C36") (pin "2") (pinfunction "2_2") (pintype "passive"))
      (node (ref "C37") (pin "2") (pinfunction "2_2") (pintype "passive"))
      (node (ref "IC8") (pin "12") (pinfunction "AVDD_12") (pintype "power_in"))
      (node (ref "R64") (pin "2") (pinfunction "2_2") (pintype "passive"))
    )
    (net (code "49") (name "Net-(Q1-PadS)") (class "Default")
      (node (ref "Q1") (pin "S") (pinfunction "S_S") (pintype "passive"))
      (node (ref "R1") (pin "2") (pinfunction "2_2") (pintype "passive"))
      (node (ref "R3") (pin "2") (pinfunction "2_2") (pintype "passive"))
      (node (ref "R4") (pin "2") (pinfunction "2_2") (pintype "passive"))
      (node (ref "R8") (pin "2") (pinfunction "2_2") (pintype "passive"))
      (node (ref "ZD1") (pin "A") (pinfunction "A_A") (pintype "passive"))
    )
    (net (code "50") (name "Net-(Q2-PadB)") (class "Default")
      (node (ref "Q2") (pin "B") (pinfunction "B_B") (pintype "passive"))
      (node (ref "R5") (pin "2") (pinfunction "2_2") (pintype "passive"))
    )
    (net (code "51") (name "Net-(Q3-PadB)") (class "Default")
      (node (ref "Q3") (pin "B") (pinfunction "B_B") (pintype "passive"))
      (node (ref "R4") (pin "1") (pinfunction "1_1") (pintype "passive"))
    )
    (net (code "52") (name "Net-(Q4-B)") (class "Default")
      (node (ref "D4") (pin "A") (pinfunction "A_A") (pintype "passive"))
      (node (ref "Q4") (pin "1") (pinfunction "B_1") (pintype "passive"))
      (node (ref "R12") (pin "2") (pinfunction "2_2") (pintype "passive"))
      (node (ref "R15") (pin "1") (pinfunction "1_1") (pintype "passive"))
    )
    (net (code "53") (name "Net-(Q4-E)") (class "Default")
      (node (ref "D1") (pin "A") (pinfunction "A_A") (pintype "passive"))
      (node (ref "Q4") (pin "3") (pinfunction "E_3") (pintype "passive"))
    )
    (net (code "54") (name "Net-(Q5-PadS)") (class "Default")
      (node (ref "Q5") (pin "S") (pinfunction "S_S") (pintype "passive"))
      (node (ref "R2") (pin "1") (pinfunction "1_1") (pintype "passive"))
      (node (ref "R5") (pin "1") (pinfunction "1_1") (pintype "passive"))
      (node (ref "R6") (pin "1") (pinfunction "1_1") (pintype "passive"))
    )
    (net (code "55") (name "Net-(Q6-E)") (class "Default")
      (node (ref "Q6") (pin "3") (pinfunction "E_3") (pintype "passive"))
      (node (ref "R14") (pin "1") (pinfunction "1_1") (pintype "passive"))
    )
    (net (code "56") (name "Net-(Q7-PadE)") (class "Default")
      (node (ref "Q7") (pin "E") (pinfunction "E_E") (pintype "passive"))
      (node (ref "R10") (pin "1") (pinfunction "1_1") (pintype "passive"))
    )
    (net (code "57") (name "Net-(Q8-PadC)") (class "Default")
      (node (ref "Q8") (pin "C") (pinfunction "C_C") (pintype "passive"))
      (node (ref "Q9") (pin "C") (pinfunction "C_C") (pintype "passive"))
      (node (ref "R15") (pin "2") (pinfunction "2_2") (pintype "passive"))
      (node (ref "R22") (pin "2") (pinfunction "2_2") (pintype "passive"))
    )
    (net (code "58") (name "Net-(Q8-PadE)") (class "Default")
      (node (ref "Q8") (pin "E") (pinfunction "E_E") (pintype "passive"))
      (node (ref "R11") (pin "1") (pinfunction "1_1") (pintype "passive"))
    )
    (net (code "59") (name "Net-(Q9-PadB)") (class "Default")
      (node (ref "Q9") (pin "B") (pinfunction "B_B") (pintype "passive"))
      (node (ref "R18") (pin "2") (pinfunction "2_2") (pintype "passive"))
      (node (ref "R8") (pin "1") (pinfunction "1_1") (pintype "passive"))
    )
    (net (code "60") (name "Net-(Q9-PadE)") (class "Default")
      (node (ref "Q9") (pin "E") (pinfunction "E_E") (pintype "passive"))
      (node (ref "R24") (pin "2") (pinfunction "2_2") (pintype "passive"))
    )
    (net (code "61") (name "Net-(Q10-PadC)") (class "Default")
      (node (ref "Q10") (pin "C") (pinfunction "C_C") (pintype "passive"))
      (node (ref "Q7") (pin "B") (pinfunction "B_B") (pintype "passive"))
      (node (ref "Q7") (pin "C") (pinfunction "C_C") (pintype "passive"))
      (node (ref "Q8") (pin "B") (pinfunction "B_B") (pintype "passive"))
    )
    (net (code "62") (name "Net-(Q10-PadE)") (class "Default")
      (node (ref "Q10") (pin "E") (pinfunction "E_E") (pintype "passive"))
      (node (ref "R27") (pin "2") (pinfunction "2_2") (pintype "passive"))
    )
    (net (code "63") (name "Net-(Q12-D)") (class "Default")
      (node (ref "Q12") (pin "3") (pinfunction "D_3") (pintype "passive"))
      (node (ref "R50") (pin "2") (pinfunction "2_2") (pintype "passive"))
      (node (ref "R52") (pin "2") (pinfunction "2_2") (pintype "passive"))
    )
    (net (code "64") (name "Net-(Q12-G)") (class "Default")
      (node (ref "D11") (pin "A") (pinfunction "A_A") (pintype "passive"))
      (node (ref "Q12") (pin "1") (pinfunction "G_1") (pintype "passive"))
      (node (ref "R49") (pin "2") (pinfunction "2_2") (pintype "passive"))
      (node (ref "X5") (pin "3") (pinfunction "S_3") (pintype "passive"))
    )
    (net (code "65") (name "Net-(Q13-D)") (class "Default")
      (node (ref "Q13") (pin "3") (pinfunction "D_3") (pintype "passive"))
      (node (ref "R58") (pin "2") (pinfunction "2_2") (pintype "passive"))
    )
    (net (code "66") (name "Net-(Q14-D)") (class "Default")
      (node (ref "Q14") (pin "3") (pinfunction "D_3") (pintype "passive"))
      (node (ref "R57") (pin "1") (pinfunction "1_1") (pintype "passive"))
    )
    (net (code "67") (name "Net-(R34-Pad2)") (class "Default")
      (node (ref "R34") (pin "2") (pinfunction "2_2") (pintype "passive"))
      (node (ref "R35") (pin "1") (pinfunction "1_1") (pintype "passive"))
    )
    (net (code "68") (name "Net-(R37-Pad1)") (class "Default")
      (node (ref "R37") (pin "1") (pinfunction "1_1") (pintype "passive"))
      (node (ref "R38") (pin "2") (pinfunction "2_2") (pintype "passive"))
    )
    (net (code "69") (name "Net-(R41-Pad1)") (class "Default")
      (node (ref "R41") (pin "1") (pinfunction "1_1") (pintype "passive"))
      (node (ref "R42") (pin "2") (pinfunction "2_2") (pintype "passive"))
    )
    (net (code "70") (name "Net-(R43-Pad1)") (class "Default")
      (node (ref "R43") (pin "1") (pinfunction "1_1") (pintype "passive"))
      (node (ref "R44") (pin "2") (pinfunction "2_2") (pintype "passive"))
    )
    (net (code "71") (name "Net-(X2F-KL)") (class "Default")
      (node (ref "C3") (pin "1") (pinfunction "1_1") (pintype "passive"))
      (node (ref "Q1") (pin "D") (pinfunction "D_D") (pintype "passive"))
      (node (ref "X2") (pin "14") (pinfunction "KL_14") (pintype "passive"))
      (node (ref "X2") (pin "15") (pinfunction "KL_15") (pintype "passive"))
      (node (ref "X2") (pin "16") (pinfunction "KL_16") (pintype "passive"))
      (node (ref "X2") (pin "17") (pinfunction "KL_17") (pintype "passive"))
    )
    (net (code "72") (name "Net-(X2J-KL)") (class "Default")
      (node (ref "C4") (pin "1") (pinfunction "1_1") (pintype "passive"))
      (node (ref "Q4") (pin "2") (pinfunction "C_2") (pintype "passive"))
      (node (ref "Q4") (pin "4") (pinfunction "C_4") (pintype "passive"))
      (node (ref "R10") (pin "2") (pinfunction "2_2") (pintype "passive"))
      (node (ref "R11") (pin "2") (pinfunction "2_2") (pintype "passive"))
      (node (ref "X2") (pin "18") (pinfunction "KL_18") (pintype "passive"))
    )
    (net (code "73") (name "Net-(X4B-S)") (class "Default")
      (node (ref "D10") (pin "C") (pinfunction "C_C") (pintype "passive"))
      (node (ref "X4") (pin "2") (pinfunction "S_2") (pintype "passive"))
    )
    (net (code "74") (name "Net-(X4D-S)") (class "Default")
      (node (ref "R47") (pin "1") (pinfunction "1_1") (pintype "passive"))
      (node (ref "X4") (pin "4") (pinfunction "S_4") (pintype "passive"))
    )
    (net (code "75") (name "Net-(X5A-S)") (class "Default")
      (node (ref "R52") (pin "1") (pinfunction "1_1") (pintype "passive"))
      (node (ref "X5") (pin "1") (pinfunction "S_1") (pintype "passive"))
    )
    (net (code "76") (name "Net-(X6A-S)") (class "Default")
      (node (ref "R57") (pin "2") (pinfunction "2_2") (pintype "passive"))
      (node (ref "X6") (pin "1") (pinfunction "S_1") (pintype "passive"))
    )
    (net (code "77") (name "Net-(X6C-S)") (class "Default")
      (node (ref "R58") (pin "1") (pinfunction "1_1") (pintype "passive"))
      (node (ref "X6") (pin "3") (pinfunction "S_3") (pintype "passive"))
    )
    (net (code "78") (name "OE_DRIVE") (class "Default")
      (node (ref "Q11") (pin "3") (pinfunction "D_3") (pintype "passive"))
      (node (ref "R27") (pin "1") (pinfunction "1_1") (pintype "passive"))
      (node (ref "R47") (pin "2") (pinfunction "2_2") (pintype "passive"))
    )
    (net (code "79") (name "OUT+") (class "Default")
      (node (ref "C1") (pin "1") (pinfunction "+_1") (pintype "passive"))
      (node (ref "C1") (pin "1.1") (pinfunction "+_1.1") (pintype "passive"))
      (node (ref "C11") (pin "1") (pinfunction "1_1") (pintype "passive"))
      (node (ref "C2") (pin "1") (pinfunction "1_1") (pintype "passive"))
      (node (ref "C24") (pin "1") (pinfunction "1_1") (pintype "passive"))
      (node (ref "C8") (pin "2") (pinfunction "2_2") (pintype "passive"))
      (node (ref "Q2") (pin "E") (pinfunction "E_E") (pintype "passive"))
      (node (ref "Q3") (pin "E") (pinfunction "E_E") (pintype "passive"))
      (node (ref "R1") (pin "1") (pinfunction "1_1") (pintype "passive"))
      (node (ref "R2") (pin "2") (pinfunction "2_2") (pintype "passive"))
      (node (ref "R9") (pin "1") (pinfunction "1_1") (pintype "passive"))
      (node (ref "X1") (pin "P$1") (pinfunction "1_P$1") (pintype "bidirectional"))
      (node (ref "X2") (pin "9") (pinfunction "KL_9") (pintype "passive"))
      (node (ref "ZD2") (pin "C") (pinfunction "1_C") (pintype "passive"))
    )
    (net (code "80") (name "OUT-") (class "Default")
      (node (ref "C1") (pin "2") (pinfunction "-_2") (pintype "passive"))
      (node (ref "C1") (pin "2.1") (pinfunction "-_2.1") (pintype "passive"))
      (node (ref "C7") (pin "1") (pinfunction "1_1") (pintype "passive"))
      (node (ref "C9") (pin "2") (pinfunction "2_2") (pintype "passive"))
      (node (ref "R32") (pin "2") (pinfunction "2_2") (pintype "passive"))
      (node (ref "R38") (pin "1") (pinfunction "1_1") (pintype "passive"))
      (node (ref "R40") (pin "1") (pinfunction "1_1") (pintype "passive"))
      (node (ref "R7") (pin "1") (pinfunction "1_1") (pintype "passive"))
      (node (ref "X1") (pin "P$2") (pinfunction "1_P$2") (pintype "bidirectional"))
      (node (ref "ZD2") (pin "A") (pinfunction "2_A") (pintype "passive"))
    )
    (net (code "81") (name "POUT-") (class "Default")
      (node (ref "R40") (pin "2") (pinfunction "2_2") (pintype "passive"))
      (node (ref "R42") (pin "1") (pinfunction "1_1") (pintype "passive"))
      (node (ref "SH1") (pin "2") (pinfunction "GND_B_2") (pintype "bidirectional"))
      (node (ref "X2") (pin "10") (pinfunction "KL_10") (pintype "passive"))
      (node (ref "X2") (pin "11") (pinfunction "KL_11") (pintype "passive"))
      (node (ref "X2") (pin "13") (pinfunction "KL_13") (pintype "passive"))
    )
    (net (code "82") (name "PREG_EN") (class "Default")
      (node (ref "D9") (pin "C") (pinfunction "C_C") (pintype "passive"))
      (node (ref "Q11") (pin "1") (pinfunction "G_1") (pintype "passive"))
      (node (ref "R48") (pin "2") (pinfunction "2_2") (pintype "passive"))
      (node (ref "X2") (pin "5") (pinfunction "KL_5") (pintype "passive"))
      (node (ref "X4") (pin "1") (pinfunction "S_1") (pintype "passive"))
    )
    (net (code "83") (name "PS_MISO") (class "Default")
      (node (ref "IC5") (pin "3") (pinfunction "SO_3") (pintype "output"))
      (node (ref "IC8") (pin "15") (pinfunction "DOUT/~{DRDY}_15") (pintype "output"))
      (node (ref "X7") (pin "9") (pinfunction "KL_9") (pintype "passive"))
    )
    (net (code "84") (name "PS_MOSI") (class "Default")
      (node (ref "IC5") (pin "2") (pinfunction "SI_2") (pintype "input"))
      (node (ref "IC6") (pin "7") (pinfunction "DIN_7") (pintype "input"))
      (node (ref "IC8") (pin "16") (pinfunction "DIN_16") (pintype "input"))
      (node (ref "X7") (pin "1") (pinfunction "KL_1") (pintype "passive"))
    )
    (net (code "85") (name "PS_SCLK") (class "Default")
      (node (ref "IC5") (pin "1") (pinfunction "SCK_1") (pintype "input"))
      (node (ref "IC6") (pin "6") (pinfunction "SCLK_6") (pintype "input"))
      (node (ref "IC8") (pin "1") (pinfunction "SCLK_1") (pintype "input"))
      (node (ref "X7") (pin "7") (pinfunction "KL_7") (pintype "passive"))
    )
    (net (code "86") (name "PWRGOOD") (class "Default")
      (node (ref "D10") (pin "A") (pinfunction "A_A") (pintype "passive"))
      (node (ref "IC5") (pin "16") (pinfunction "GP6_16") (pintype "bidirectional"))
      (node (ref "X2") (pin "1") (pinfunction "KL_1") (pintype "passive"))
    )
    (net (code "87") (name "SENSE+") (class "Default")
      (node (ref "C6") (pin "1") (pinfunction "1_1") (pintype "passive"))
      (node (ref "R21") (pin "2") (pinfunction "2_2") (pintype "passive"))
      (node (ref "R9") (pin "2") (pinfunction "2_2") (pintype "passive"))
      (node (ref "X1") (pin "P$3") (pinfunction "1_P$3") (pintype "bidirectional"))
    )
    (net (code "88") (name "SENSE-") (class "Default")
      (node (ref "C12") (pin "1") (pinfunction "1_1") (pintype "passive"))
      (node (ref "R31") (pin "2") (pinfunction "2_2") (pintype "passive"))
      (node (ref "R32") (pin "1") (pinfunction "1_1") (pintype "passive"))
      (node (ref "X1") (pin "P$4") (pinfunction "1_P$4") (pintype "bidirectional"))
    )
    (net (code "89") (name "SET_OE") (class "Default")
      (node (ref "D9") (pin "A") (pinfunction "A_A") (pintype "passive"))
      (node (ref "IC5") (pin "17") (pinfunction "GP7_17") (pintype "bidirectional"))
    )
    (net (code "90") (name "TEMP_FREQ") (class "Default")
      (node (ref "IC5") (pin "13") (pinfunction "GP3_13") (pintype "bidirectional"))
      (node (ref "X2") (pin "3") (pinfunction "KL_3") (pintype "passive"))
    )
    (net (code "91") (name "U_MON") (class "Default")
      (node (ref "IC1") (pin "7") (pinfunction "OUT_7") (pintype "output"))
      (node (ref "IC8") (pin "10") (pinfunction "AIN1_10") (pintype "input"))
      (node (ref "R25") (pin "1") (pinfunction "1_1") (pintype "passive"))
      (node (ref "R26") (pin "1") (pinfunction "1_1") (pintype "passive"))
    )
    (net (code "92") (name "U_SERVO") (class "Default")
      (node (ref "D5") (pin "C") (pinfunction "C_C") (pintype "passive"))
      (node (ref "D6") (pin "A") (pinfunction "A_A") (pintype "passive"))
      (node (ref "IC1") (pin "1") (pinfunction "OUT_1") (pintype "output"))
      (node (ref "R28") (pin "2") (pinfunction "2_2") (pintype "passive"))
      (node (ref "R51") (pin "1") (pinfunction "1_1") (pintype "passive"))
    )
    (net (code "93") (name "U_SET") (class "Default")
      (node (ref "R23") (pin "1") (pinfunction "1_1") (pintype "passive"))
      (node (ref "X3") (pin "3") (pinfunction "1_3") (pintype "passive"))
    )
    (net (code "94") (name "U_SET_IN") (class "Default")
      (node (ref "IC6") (pin "4") (pinfunction "VOUTA_4") (pintype "output"))
      (node (ref "IC8") (pin "11") (pinfunction "AIN0/REFP1_11") (pintype "input"))
      (node (ref "X3") (pin "1") (pinfunction "1_1") (pintype "passive"))
    )
    (net (code "95") (name "V+") (class "Default")
      (node (ref "C13") (pin "2") (pinfunction "2_2") (pintype "passive"))
      (node (ref "C14") (pin "1") (pinfunction "1_1") (pintype "passive"))
      (node (ref "C15") (pin "2") (pinfunction "2_2") (pintype "passive"))
      (node (ref "C16") (pin "2") (pinfunction "2_2") (pintype "passive"))
      (node (ref "C17") (pin "2") (pinfunction "2_2") (pintype "passive"))
      (node (ref "C25") (pin "2") (pinfunction "2_2") (pintype "passive"))
      (node (ref "IC1") (pin "8") (pinfunction "V+_8") (pintype "power_in"))
      (node (ref "IC2") (pin "8") (pinfunction "V+_8") (pintype "power_in"))
      (node (ref "IC3") (pin "7") (pinfunction "V+_7") (pintype "power_in"))
      (node (ref "IC4") (pin "3") (pinfunction "V+_3") (pintype "power_in"))
      (node (ref "R54") (pin "2") (pinfunction "2_2") (pintype "passive"))
      (node (ref "X2") (pin "6") (pinfunction "KL_6") (pintype "passive"))
    )
    (net (code "96") (name "V-") (class "Default")
      (node (ref "C18") (pin "2") (pinfunction "2_2") (pintype "passive"))
      (node (ref "C19") (pin "2") (pinfunction "2_2") (pintype "passive"))
      (node (ref "C20") (pin "1") (pinfunction "1_1") (pintype "passive"))
      (node (ref "C21") (pin "2") (pinfunction "2_2") (pintype "passive"))
      (node (ref "C22") (pin "2") (pinfunction "2_2") (pintype "passive"))
      (node (ref "C26") (pin "2") (pinfunction "2_2") (pintype "passive"))
      (node (ref "IC1") (pin "4") (pinfunction "V-_4") (pintype "power_in"))
      (node (ref "IC2") (pin "4") (pinfunction "V-_4") (pintype "power_in"))
      (node (ref "IC3") (pin "4") (pinfunction "V-_4") (pintype "power_in"))
      (node (ref "IC4") (pin "12") (pinfunction "GND_12") (pintype "power_in"))
      (node (ref "R61") (pin "1") (pinfunction "1_1") (pintype "passive"))
      (node (ref "X2") (pin "4") (pinfunction "KL_4") (pintype "passive"))
    )
    (net (code "97") (name "unconnected-(IC7-TEMP-Pad3)") (class "Default")
      (node (ref "IC7") (pin "3") (pinfunction "TEMP_3") (pintype "input"))
    )
    (net (code "98") (name "~{CC_ACTIVE}") (class "Default")
      (node (ref "IC5") (pin "12") (pinfunction "GP2_12") (pintype "bidirectional"))
      (node (ref "Q14") (pin "1") (pinfunction "G_1") (pintype "passive"))
      (node (ref "R60") (pin "1") (pinfunction "1_1") (pintype "passive"))
      (node (ref "R62") (pin "2") (pinfunction "2_2") (pintype "passive"))
    )
    (net (code "99") (name "~{CV_ACTIVE}") (class "Default")
      (node (ref "IC5") (pin "15") (pinfunction "GP5_15") (pintype "bidirectional"))
      (node (ref "Q13") (pin "1") (pinfunction "G_1") (pintype "passive"))
      (node (ref "R53") (pin "1") (pinfunction "1_1") (pintype "passive"))
      (node (ref "R55") (pin "2") (pinfunction "2_2") (pintype "passive"))
    )
    (net (code "100") (name "~{DP_DRIVE}") (class "Default")
      (node (ref "Q6") (pin "1") (pinfunction "B_1") (pintype "passive"))
      (node (ref "R13") (pin "1") (pinfunction "1_1") (pintype "passive"))
      (node (ref "R50") (pin "1") (pinfunction "1_1") (pintype "passive"))
    )
    (net (code "101") (name "~{INT}") (class "Default")
      (node (ref "JP1") (pin "3") (pinfunction "3_3") (pintype "passive"))
      (node (ref "X7") (pin "8") (pinfunction "KL_8") (pintype "passive"))
    )
    (net (code "102") (name "~{PS_DRDY}") (class "Default")
      (node (ref "IC8") (pin "14") (pinfunction "~{DRDY}_14") (pintype "output"))
      (node (ref "JP1") (pin "2") (pinfunction "2_2") (pintype "passive"))
    )
    (net (code "103") (name "~{PS_RESET}") (class "Default")
      (node (ref "IC5") (pin "6") (pinfunction "~{RESET}_6") (pintype "input"))
      (node (ref "X7") (pin "5") (pinfunction "KL_5") (pintype "passive"))
    )
    (net (code "104") (name "~{SET_100%}") (class "Default")
      (node (ref "IC5") (pin "14") (pinfunction "GP4_14") (pintype "bidirectional"))
      (node (ref "X2") (pin "7") (pinfunction "KL_7") (pintype "passive"))
    )
    (net (code "105") (name "~{SET_DP}") (class "Default")
      (node (ref "D11") (pin "C") (pinfunction "C_C") (pintype "passive"))
      (node (ref "IC5") (pin "11") (pinfunction "GP1_11") (pintype "bidirectional"))
    )
  )
)
